# vineseenon.net
KiCad netlist of a schematic drawn in EAGLE
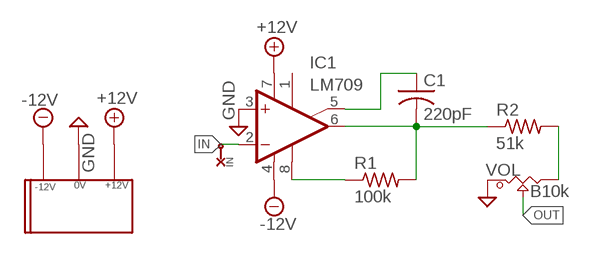
[diagram p0: schematic, sheet 1]

(export (version "E")
  (design (tool "Eeschema 10.0.6"))
  (components
    (comp (ref "C1")
      (value "220pF")
      (footprint "eagle-import:C0603")
      (libsource (lib "eagle-import") (part "C-USC0603"))
    )
    (comp (ref "IC1")
      (value "LM709")
      (footprint "eagle-import:DIL08")
      (libsource (lib "eagle-import") (part "TL061P"))
    )
    (comp (ref "IN")
      (value "PAD")
      (footprint "eagle-import:1PAD_B")
      (libsource (lib "eagle-import") (part "PAD"))
    )
    (comp (ref "R1")
      (value "100k")
      (footprint "eagle-import:R0603")
      (libsource (lib "eagle-import") (part "R-US_R0603"))
    )
    (comp (ref "R2")
      (value "51k")
      (footprint "eagle-import:R0603")
      (libsource (lib "eagle-import") (part "R-US_R0603"))
    )
    (comp (ref "U$1")
      (value "EURO_POW_CEH")
      (footprint "eagle-import:EURO_POW_CEH")
      (libsource (lib "eagle-import") (part "EURO_POW_CEH"))
    )
    (comp (ref "VOL")
      (value "B10k")
      (footprint "eagle-import:POT_9MM_SMD")
      (libsource (lib "eagle-import") (part "POT_9MM_SMD"))
    )
  )
  (nets
    (net (code "1") (name "+12V") (class "Default")
      (node (ref "IC1") (pin "7") (pinfunction "V+_7") (pintype "power_in"))
      (node (ref "U$1") (pin "+12V") (pinfunction "+12V_+12V") (pintype "bidirectional"))
    )
    (net (code "2") (name "-12V") (class "Default")
      (node (ref "IC1") (pin "4") (pinfunction "V-_4") (pintype "power_in"))
      (node (ref "U$1") (pin "-12V") (pinfunction "-12V_-12V") (pintype "bidirectional"))
    )
    (net (code "3") (name "GND") (class "Default")
      (node (ref "IC1") (pin "3") (pinfunction "+IN_3") (pintype "input"))
      (node (ref "U$1") (pin "GND") (pinfunction "GND_GND") (pintype "bidirectional"))
      (node (ref "VOL") (pin "1") (pinfunction "1_1") (pintype "bidirectional"))
    )
    (net (code "4") (name "IN") (class "Default")
      (node (ref "IC1") (pin "2") (pinfunction "-IN_2") (pintype "input"))
      (node (ref "IN") (pin "1") (pinfunction "1_1") (pintype "bidirectional"))
    )
    (net (code "5") (name "Net-(IC1-ON2)") (class "Default")
      (node (ref "C1") (pin "1") (pinfunction "1_1") (pintype "passive"))
      (node (ref "IC1") (pin "5") (pinfunction "ON2_5") (pintype "passive"))
    )
    (net (code "6") (name "Net-(IC1-OPT)") (class "Default")
      (node (ref "IC1") (pin "8") (pinfunction "OPT_8") (pintype "passive"))
      (node (ref "R1") (pin "1") (pinfunction "1_1") (pintype "passive"))
    )
    (net (code "7") (name "Net-(IC1-OUT)") (class "Default")
      (node (ref "C1") (pin "2") (pinfunction "2_2") (pintype "passive"))
      (node (ref "IC1") (pin "6") (pinfunction "OUT_6") (pintype "output"))
      (node (ref "R1") (pin "2") (pinfunction "2_2") (pintype "passive"))
      (node (ref "R2") (pin "1") (pinfunction "1_1") (pintype "passive"))
    )
    (net (code "8") (name "Net-(R2-Pad2)") (class "Default")
      (node (ref "R2") (pin "2") (pinfunction "2_2") (pintype "passive"))
      (node (ref "VOL") (pin "3") (pinfunction "3_3") (pintype "bidirectional"))
    )
    (net (code "9") (name "OUT") (class "Default")
      (node (ref "VOL") (pin "2") (pinfunction "2_2") (pintype "bidirectional"))
    )
    (net (code "10") (name "unconnected-(IC1-ON1-Pad1)") (class "Default")
      (node (ref "IC1") (pin "1") (pinfunction "ON1_1") (pintype "passive"))
    )
  )
)
